# Sheet2.net
KiCad netlist of a schematic drawn in Altium Designer
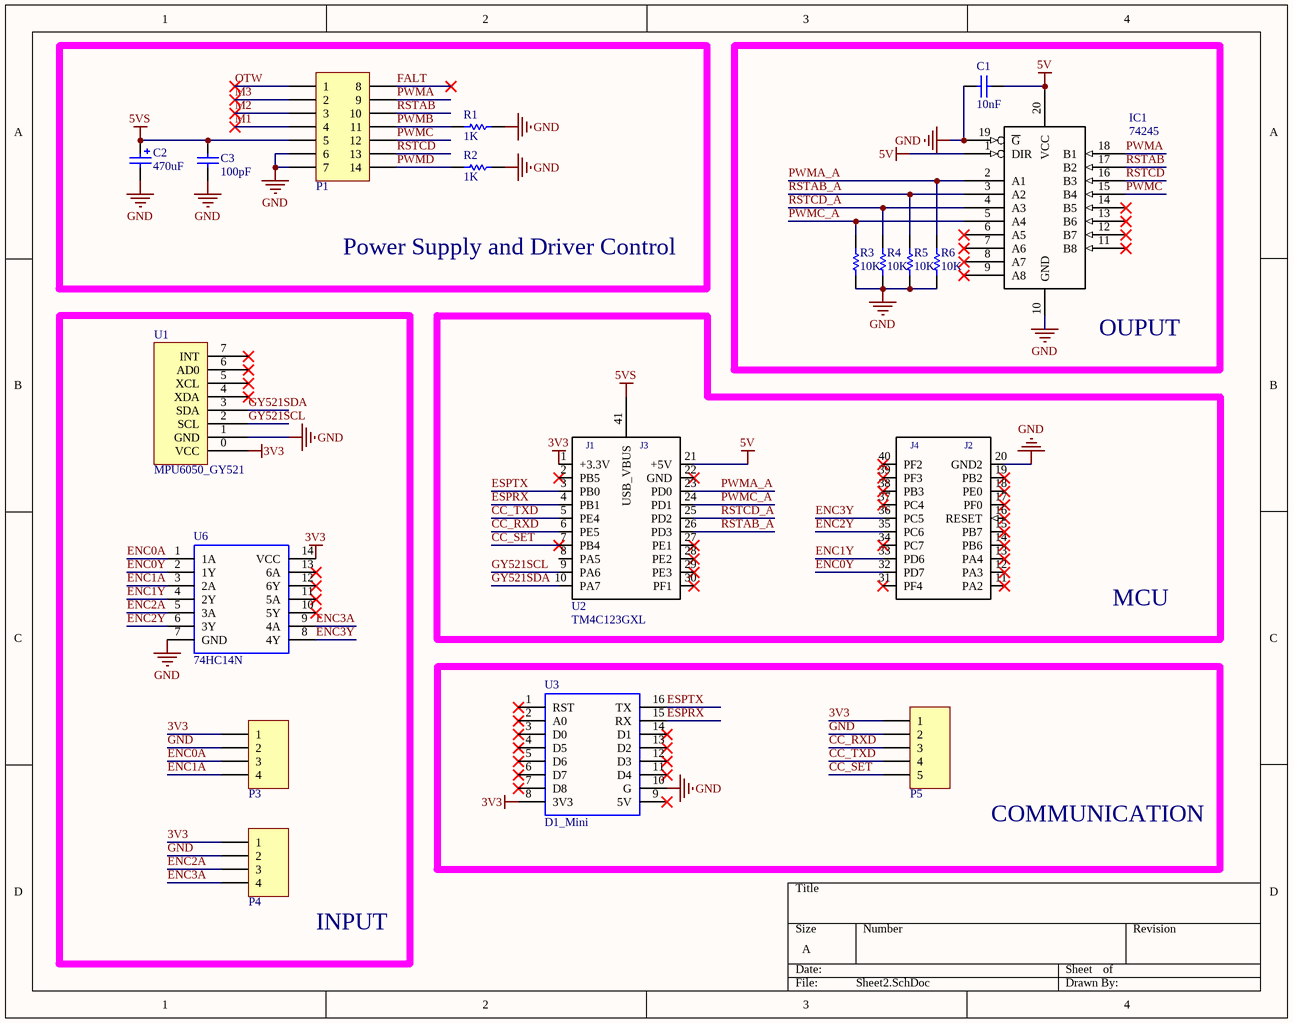
[diagram p0: Sheet2.SchDoc]

(export (version "E")
  (design (tool "Eeschema 10.0.6"))
  (components
    (comp (ref "C1")
      (value "10nF")
      (footprint "CAP-SM-0805")
      (description "Capacitor")
      (fields (field (name "Comment") "Cap Non-Pol SMD"))
      (libsource (lib "PIF_Library") (part "Cap Non-Pol SMD"))
    )
    (comp (ref "C2")
      (value "470uF")
      (footprint "CP1/2")
      (description "Polarized Capacitor (Radial)")
      (fields (field (name "Comment") "Cap Pol"))
      (libsource (lib "PIF_Library") (part "Cap Pol"))
    )
    (comp (ref "C3")
      (value "100pF")
      (footprint "CAP-SM-0805")
      (description "Capacitor")
      (fields (field (name "Comment") "Cap Non-Pol SMD"))
      (libsource (lib "PIF_Library") (part "Cap Non-Pol SMD"))
    )
    (comp (ref "IC1")
      (value "74245")
      (footprint "DIP20")
      (description "Octal bus tranceiver; 3-state")
      (fields (field (name "COPYRIGHT BY") "VanDungEvn@gmail.com"))
      (libsource (lib "My Library") (part "74245_1"))
    )
    (comp (ref "P1")
      (value "Header 7X2")
      (footprint "JP7X2")
      (description "Header, 7-Pin, Dual row")
      (fields (field (name "PUBLISHER") "Altium Limited"))
      (libsource (lib "PIF_Library") (part "Header 7X2"))
    )
    (comp (ref "P3")
      (value "Header 4H")
      (footprint "JP4H")
      (description "Header, 4-Pin, Right Angle")
      (fields (field (name "PUBLISHER") "Altium Limited"))
      (libsource (lib "PIF_Library") (part "Header 4H"))
    )
    (comp (ref "P4")
      (value "Header 4H")
      (footprint "JP4H")
      (description "Header, 4-Pin, Right Angle")
      (fields (field (name "PUBLISHER") "Altium Limited"))
      (libsource (lib "PIF_Library") (part "Header 4H"))
    )
    (comp (ref "P5")
      (value "Header 5")
      (footprint "JP5")
      (description "Header, 5-Pin")
      (fields (field (name "PUBLISHER") "Altium Limited"))
      (libsource (lib "PIF_Library") (part "Header 5"))
    )
    (comp (ref "R1")
      (value "1K")
      (footprint "RES 1/2W")
      (description "Resistor")
      (fields (field (name "Comment") "RESISTOR"))
      (libsource (lib "PIF_Library") (part "RESISTOR"))
    )
    (comp (ref "R2")
      (value "1K")
      (footprint "RES 1/2W")
      (description "Resistor")
      (fields (field (name "Comment") "RESISTOR"))
      (libsource (lib "PIF_Library") (part "RESISTOR"))
    )
    (comp (ref "R3")
      (value "10K")
      (footprint "RES 1/2W")
      (description "Resistor")
      (fields (field (name "Comment") "RESISTOR"))
      (libsource (lib "PIF_Library") (part "RESISTOR"))
    )
    (comp (ref "R4")
      (value "10K")
      (footprint "RES 1/2W")
      (description "Resistor")
      (fields (field (name "Comment") "RESISTOR"))
      (libsource (lib "PIF_Library") (part "RESISTOR"))
    )
    (comp (ref "R5")
      (value "10K")
      (footprint "RES 1/2W")
      (description "Resistor")
      (fields (field (name "Comment") "RESISTOR"))
      (libsource (lib "PIF_Library") (part "RESISTOR"))
    )
    (comp (ref "R6")
      (value "10K")
      (footprint "RES 1/2W")
      (description "Resistor")
      (fields (field (name "Comment") "RESISTOR"))
      (libsource (lib "PIF_Library") (part "RESISTOR"))
    )
    (comp (ref "U1")
      (value "MPU6050_GY521")
      (footprint "MPU6050_GY521")
      (libsource (lib "AltiumLib") (part "MPU6050_GY521"))
    )
    (comp (ref "U2")
      (value "TM4C123GXL")
      (footprint "EK-TM4C123GXL")
      (libsource (lib "AltiumLib") (part "EK-TM4C123GXL"))
    )
    (comp (ref "U3") (value "D1_Mini") (footprint "D1_Mini") (libsource (lib "AltiumLib") (part "D1_Mini")))
    (comp (ref "U6") (value "74HC14N") (footprint "74HC14N") (libsource (lib "AltiumLib") (part "74HC14N")))
  )
  (nets
    (net (code "1") (name "/CC_RXD") (class "Default")
      (node (ref "P5") (pin "3") (pinfunction "3_3") (pintype "passive"))
      (node (ref "U2") (pin "6") (pinfunction "PE5_6") (pintype "bidirectional"))
    )
    (net (code "2") (name "/CC_SET") (class "Default")
      (node (ref "P5") (pin "5") (pinfunction "5_5") (pintype "passive"))
      (node (ref "U2") (pin "7") (pinfunction "PB4_7") (pintype "bidirectional"))
    )
    (net (code "3") (name "/CC_TXD") (class "Default")
      (node (ref "P5") (pin "4") (pinfunction "4_4") (pintype "passive"))
      (node (ref "U2") (pin "5") (pinfunction "PE4_5") (pintype "bidirectional"))
    )
    (net (code "4") (name "/ENC0A") (class "Default")
      (node (ref "P3") (pin "3") (pinfunction "3_3") (pintype "passive"))
      (node (ref "U6") (pin "1") (pinfunction "1A_1") (pintype "passive"))
    )
    (net (code "5") (name "/ENC0Y") (class "Default")
      (node (ref "U2") (pin "32") (pinfunction "PD7_32") (pintype "bidirectional"))
      (node (ref "U6") (pin "2") (pinfunction "1Y_2") (pintype "passive"))
    )
    (net (code "6") (name "/ENC1A") (class "Default")
      (node (ref "P3") (pin "4") (pinfunction "4_4") (pintype "passive"))
      (node (ref "U6") (pin "3") (pinfunction "2A_3") (pintype "passive"))
    )
    (net (code "7") (name "/ENC1Y") (class "Default")
      (node (ref "U2") (pin "33") (pinfunction "PD6_33") (pintype "bidirectional"))
      (node (ref "U6") (pin "4") (pinfunction "2Y_4") (pintype "passive"))
    )
    (net (code "8") (name "/ENC2A") (class "Default")
      (node (ref "P4") (pin "3") (pinfunction "3_3") (pintype "passive"))
      (node (ref "U6") (pin "5") (pinfunction "3A_5") (pintype "passive"))
    )
    (net (code "9") (name "/ENC2Y") (class "Default")
      (node (ref "U2") (pin "35") (pinfunction "PC6_35") (pintype "bidirectional"))
      (node (ref "U6") (pin "6") (pinfunction "3Y_6") (pintype "passive"))
    )
    (net (code "10") (name "/ENC3A") (class "Default")
      (node (ref "P4") (pin "4") (pinfunction "4_4") (pintype "passive"))
      (node (ref "U6") (pin "9") (pinfunction "4A_9") (pintype "passive"))
    )
    (net (code "11") (name "/ENC3Y") (class "Default")
      (node (ref "U2") (pin "36") (pinfunction "PC5_36") (pintype "bidirectional"))
      (node (ref "U6") (pin "8") (pinfunction "4Y_8") (pintype "passive"))
    )
    (net (code "12") (name "/ESPRX") (class "Default")
      (node (ref "U2") (pin "4") (pinfunction "PB1_4") (pintype "bidirectional"))
      (node (ref "U3") (pin "15") (pinfunction "RX_15") (pintype "passive"))
    )
    (net (code "13") (name "/ESPTX") (class "Default")
      (node (ref "U2") (pin "3") (pinfunction "PB0_3") (pintype "bidirectional"))
      (node (ref "U3") (pin "16") (pinfunction "TX_16") (pintype "passive"))
    )
    (net (code "14") (name "/FALT") (class "Default")
      (node (ref "P1") (pin "8") (pinfunction "8_8") (pintype "passive+no_connect"))
    )
    (net (code "15") (name "/GY521SCL") (class "Default")
      (node (ref "U1") (pin "2") (pinfunction "SCL_2") (pintype "passive"))
      (node (ref "U2") (pin "9") (pinfunction "PA6_9") (pintype "bidirectional"))
    )
    (net (code "16") (name "/GY521SDA") (class "Default")
      (node (ref "U1") (pin "3") (pinfunction "SDA_3") (pintype "passive"))
      (node (ref "U2") (pin "10") (pinfunction "PA7_10") (pintype "bidirectional"))
    )
    (net (code "17") (name "/M1") (class "Default")
      (node (ref "P1") (pin "4") (pinfunction "4_4") (pintype "passive+no_connect"))
    )
    (net (code "18") (name "/M2") (class "Default")
      (node (ref "P1") (pin "3") (pinfunction "3_3") (pintype "passive+no_connect"))
    )
    (net (code "19") (name "/M3") (class "Default")
      (node (ref "P1") (pin "2") (pinfunction "2_2") (pintype "passive+no_connect"))
    )
    (net (code "20") (name "/OTW") (class "Default")
      (node (ref "P1") (pin "1") (pinfunction "1_1") (pintype "passive+no_connect"))
    )
    (net (code "21") (name "/PWMA") (class "Default")
      (node (ref "IC1") (pin "18") (pinfunction "B1_18") (pintype "input"))
      (node (ref "P1") (pin "9") (pinfunction "9_9") (pintype "passive"))
    )
    (net (code "22") (name "/PWMA_A") (class "Default")
      (node (ref "IC1") (pin "2") (pinfunction "A1_2") (pintype "tri_state"))
      (node (ref "R6") (pin "2") (pinfunction "2_2") (pintype "passive"))
      (node (ref "U2") (pin "23") (pinfunction "PD0_23") (pintype "bidirectional"))
    )
    (net (code "23") (name "/PWMB") (class "Default")
      (node (ref "P1") (pin "11") (pinfunction "11_11") (pintype "passive"))
      (node (ref "R1") (pin "1") (pinfunction "1_1") (pintype "passive"))
    )
    (net (code "24") (name "/PWMC") (class "Default")
      (node (ref "IC1") (pin "15") (pinfunction "B4_15") (pintype "input"))
      (node (ref "P1") (pin "12") (pinfunction "12_12") (pintype "passive"))
    )
    (net (code "25") (name "/PWMC_A") (class "Default")
      (node (ref "IC1") (pin "5") (pinfunction "A4_5") (pintype "tri_state"))
      (node (ref "R3") (pin "2") (pinfunction "2_2") (pintype "passive"))
      (node (ref "U2") (pin "24") (pinfunction "PD1_24") (pintype "bidirectional"))
    )
    (net (code "26") (name "/PWMD") (class "Default")
      (node (ref "P1") (pin "14") (pinfunction "14_14") (pintype "passive"))
      (node (ref "R2") (pin "1") (pinfunction "1_1") (pintype "passive"))
    )
    (net (code "27") (name "/RSTAB") (class "Default")
      (node (ref "IC1") (pin "17") (pinfunction "B2_17") (pintype "input"))
      (node (ref "P1") (pin "10") (pinfunction "10_10") (pintype "passive"))
    )
    (net (code "28") (name "/RSTAB_A") (class "Default")
      (node (ref "IC1") (pin "3") (pinfunction "A2_3") (pintype "tri_state"))
      (node (ref "R5") (pin "2") (pinfunction "2_2") (pintype "passive"))
      (node (ref "U2") (pin "26") (pinfunction "PD3_26") (pintype "bidirectional"))
    )
    (net (code "29") (name "/RSTCD") (class "Default")
      (node (ref "IC1") (pin "16") (pinfunction "B3_16") (pintype "input"))
      (node (ref "P1") (pin "13") (pinfunction "13_13") (pintype "passive"))
    )
    (net (code "30") (name "/RSTCD_A") (class "Default")
      (node (ref "IC1") (pin "4") (pinfunction "A3_4") (pintype "tri_state"))
      (node (ref "R4") (pin "2") (pinfunction "2_2") (pintype "passive"))
      (node (ref "U2") (pin "25") (pinfunction "PD2_25") (pintype "bidirectional"))
    )
    (net (code "31") (name "3V3") (class "Default")
      (node (ref "P3") (pin "1") (pinfunction "1_1") (pintype "passive"))
      (node (ref "P4") (pin "1") (pinfunction "1_1") (pintype "passive"))
      (node (ref "P5") (pin "1") (pinfunction "1_1") (pintype "passive"))
      (node (ref "U1") (pin "0") (pinfunction "VCC_0") (pintype "power_in"))
      (node (ref "U2") (pin "1") (pinfunction "+3.3V_1") (pintype "power_in"))
      (node (ref "U3") (pin "8") (pinfunction "3V3_8") (pintype "passive"))
      (node (ref "U6") (pin "14") (pinfunction "VCC_14") (pintype "passive"))
    )
    (net (code "32") (name "5V") (class "Default")
      (node (ref "C1") (pin "2") (pinfunction "2_2") (pintype "passive"))
      (node (ref "IC1") (pin "1") (pinfunction "DIR_1") (pintype "input"))
      (node (ref "IC1") (pin "20") (pinfunction "VCC_20") (pintype "power_in"))
      (node (ref "U2") (pin "21") (pinfunction "+5V_21") (pintype "power_in"))
    )
    (net (code "33") (name "5VS") (class "Default")
      (node (ref "C2") (pin "1") (pinfunction "1_1") (pintype "passive"))
      (node (ref "C3") (pin "2") (pinfunction "2_2") (pintype "passive"))
      (node (ref "P1") (pin "5") (pinfunction "5_5") (pintype "passive"))
      (node (ref "U2") (pin "41") (pinfunction "USB_VBUS_41") (pintype "passive"))
    )
    (net (code "34") (name "GND") (class "Default")
      (node (ref "C1") (pin "1") (pinfunction "1_1") (pintype "passive"))
      (node (ref "C2") (pin "2") (pinfunction "2_2") (pintype "passive"))
      (node (ref "C3") (pin "1") (pinfunction "1_1") (pintype "passive"))
      (node (ref "IC1") (pin "10") (pinfunction "GND_10") (pintype "power_in"))
      (node (ref "IC1") (pin "19") (pinfunction "~{G}_19") (pintype "input"))
      (node (ref "P1") (pin "6") (pinfunction "6_6") (pintype "passive"))
      (node (ref "P1") (pin "7") (pinfunction "7_7") (pintype "passive"))
      (node (ref "P3") (pin "2") (pinfunction "2_2") (pintype "passive"))
      (node (ref "P4") (pin "2") (pinfunction "2_2") (pintype "passive"))
      (node (ref "P5") (pin "2") (pinfunction "2_2") (pintype "passive"))
      (node (ref "R1") (pin "2") (pinfunction "2_2") (pintype "passive"))
      (node (ref "R2") (pin "2") (pinfunction "2_2") (pintype "passive"))
      (node (ref "R3") (pin "1") (pinfunction "1_1") (pintype "passive"))
      (node (ref "R4") (pin "1") (pinfunction "1_1") (pintype "passive"))
      (node (ref "R5") (pin "1") (pinfunction "1_1") (pintype "passive"))
      (node (ref "R6") (pin "1") (pinfunction "1_1") (pintype "passive"))
      (node (ref "U1") (pin "1") (pinfunction "GND_1") (pintype "power_in"))
      (node (ref "U2") (pin "20") (pinfunction "GND2_20") (pintype "power_in"))
      (node (ref "U3") (pin "10") (pinfunction "G_10") (pintype "passive"))
      (node (ref "U6") (pin "7") (pinfunction "GND_7") (pintype "passive"))
    )
    (net (code "35") (name "unconnected-(IC1-A5-Pad6)") (class "Default")
      (node (ref "IC1") (pin "6") (pinfunction "A5_6") (pintype "tri_state+no_connect"))
    )
    (net (code "36") (name "unconnected-(IC1-A6-Pad7)") (class "Default")
      (node (ref "IC1") (pin "7") (pinfunction "A6_7") (pintype "tri_state+no_connect"))
    )
    (net (code "37") (name "unconnected-(IC1-A7-Pad8)") (class "Default")
      (node (ref "IC1") (pin "8") (pinfunction "A7_8") (pintype "tri_state+no_connect"))
    )
    (net (code "38") (name "unconnected-(IC1-A8-Pad9)") (class "Default")
      (node (ref "IC1") (pin "9") (pinfunction "A8_9") (pintype "tri_state+no_connect"))
    )
    (net (code "39") (name "unconnected-(IC1-B5-Pad14)") (class "Default")
      (node (ref "IC1") (pin "14") (pinfunction "B5_14") (pintype "input+no_connect"))
    )
    (net (code "40") (name "unconnected-(IC1-B6-Pad13)") (class "Default")
      (node (ref "IC1") (pin "13") (pinfunction "B6_13") (pintype "input+no_connect"))
    )
    (net (code "41") (name "unconnected-(IC1-B7-Pad12)") (class "Default")
      (node (ref "IC1") (pin "12") (pinfunction "B7_12") (pintype "input+no_connect"))
    )
    (net (code "42") (name "unconnected-(IC1-B8-Pad11)") (class "Default")
      (node (ref "IC1") (pin "11") (pinfunction "B8_11") (pintype "input+no_connect"))
    )
    (net (code "43") (name "unconnected-(U1-AD0-Pad6)") (class "Default")
      (node (ref "U1") (pin "6") (pinfunction "AD0_6") (pintype "passive+no_connect"))
    )
    (net (code "44") (name "unconnected-(U1-INT-Pad7)") (class "Default")
      (node (ref "U1") (pin "7") (pinfunction "INT_7") (pintype "passive+no_connect"))
    )
    (net (code "45") (name "unconnected-(U1-XCL-Pad5)") (class "Default")
      (node (ref "U1") (pin "5") (pinfunction "XCL_5") (pintype "passive+no_connect"))
    )
    (net (code "46") (name "unconnected-(U1-XDA-Pad4)") (class "Default")
      (node (ref "U1") (pin "4") (pinfunction "XDA_4") (pintype "passive+no_connect"))
    )
    (net (code "47") (name "unconnected-(U2-GND-Pad22)") (class "Default")
      (node (ref "U2") (pin "22") (pinfunction "GND_22") (pintype "power_in+no_connect"))
    )
    (net (code "48") (name "unconnected-(U2-PA2-Pad11)") (class "Default")
      (node (ref "U2") (pin "11") (pinfunction "PA2_11") (pintype "bidirectional+no_connect"))
    )
    (net (code "49") (name "unconnected-(U2-PA3-Pad12)") (class "Default")
      (node (ref "U2") (pin "12") (pinfunction "PA3_12") (pintype "bidirectional+no_connect"))
    )
    (net (code "50") (name "unconnected-(U2-PA4-Pad13)") (class "Default")
      (node (ref "U2") (pin "13") (pinfunction "PA4_13") (pintype "bidirectional+no_connect"))
    )
    (net (code "51") (name "unconnected-(U2-PA5-Pad8)") (class "Default")
      (node (ref "U2") (pin "8") (pinfunction "PA5_8") (pintype "bidirectional"))
    )
    (net (code "52") (name "unconnected-(U2-PB2-Pad19)") (class "Default")
      (node (ref "U2") (pin "19") (pinfunction "PB2_19") (pintype "bidirectional+no_connect"))
    )
    (net (code "53") (name "unconnected-(U2-PB3-Pad38)") (class "Default")
      (node (ref "U2") (pin "38") (pinfunction "PB3_38") (pintype "bidirectional+no_connect"))
    )
    (net (code "54") (name "unconnected-(U2-PB5-Pad2)") (class "Default")
      (node (ref "U2") (pin "2") (pinfunction "PB5_2") (pintype "bidirectional+no_connect"))
    )
    (net (code "55") (name "unconnected-(U2-PB6-Pad14)") (class "Default")
      (node (ref "U2") (pin "14") (pinfunction "PB6_14") (pintype "bidirectional+no_connect"))
    )
    (net (code "56") (name "unconnected-(U2-PB7-Pad15)") (class "Default")
      (node (ref "U2") (pin "15") (pinfunction "PB7_15") (pintype "bidirectional+no_connect"))
    )
    (net (code "57") (name "unconnected-(U2-PC4-Pad37)") (class "Default")
      (node (ref "U2") (pin "37") (pinfunction "PC4_37") (pintype "bidirectional+no_connect"))
    )
    (net (code "58") (name "unconnected-(U2-PC7-Pad34)") (class "Default")
      (node (ref "U2") (pin "34") (pinfunction "PC7_34") (pintype "bidirectional+no_connect"))
    )
    (net (code "59") (name "unconnected-(U2-PE0-Pad18)") (class "Default")
      (node (ref "U2") (pin "18") (pinfunction "PE0_18") (pintype "bidirectional+no_connect"))
    )
    (net (code "60") (name "unconnected-(U2-PE1-Pad27)") (class "Default")
      (node (ref "U2") (pin "27") (pinfunction "PE1_27") (pintype "bidirectional+no_connect"))
    )
    (net (code "61") (name "unconnected-(U2-PE2-Pad28)") (class "Default")
      (node (ref "U2") (pin "28") (pinfunction "PE2_28") (pintype "bidirectional+no_connect"))
    )
    (net (code "62") (name "unconnected-(U2-PE3-Pad29)") (class "Default")
      (node (ref "U2") (pin "29") (pinfunction "PE3_29") (pintype "bidirectional+no_connect"))
    )
    (net (code "63") (name "unconnected-(U2-PF0-Pad17)") (class "Default")
      (node (ref "U2") (pin "17") (pinfunction "PF0_17") (pintype "bidirectional+no_connect"))
    )
    (net (code "64") (name "unconnected-(U2-PF1-Pad30)") (class "Default")
      (node (ref "U2") (pin "30") (pinfunction "PF1_30") (pintype "bidirectional+no_connect"))
    )
    (net (code "65") (name "unconnected-(U2-PF2-Pad40)") (class "Default")
      (node (ref "U2") (pin "40") (pinfunction "PF2_40") (pintype "bidirectional+no_connect"))
    )
    (net (code "66") (name "unconnected-(U2-PF3-Pad39)") (class "Default")
      (node (ref "U2") (pin "39") (pinfunction "PF3_39") (pintype "bidirectional+no_connect"))
    )
    (net (code "67") (name "unconnected-(U2-PF4-Pad31)") (class "Default")
      (node (ref "U2") (pin "31") (pinfunction "PF4_31") (pintype "bidirectional+no_connect"))
    )
    (net (code "68") (name "unconnected-(U2-RESET-Pad16)") (class "Default")
      (node (ref "U2") (pin "16") (pinfunction "RESET_16") (pintype "input+no_connect"))
    )
    (net (code "69") (name "unconnected-(U3-5V-Pad9)") (class "Default")
      (node (ref "U3") (pin "9") (pinfunction "5V_9") (pintype "passive+no_connect"))
    )
    (net (code "70") (name "unconnected-(U3-A0-Pad2)") (class "Default")
      (node (ref "U3") (pin "2") (pinfunction "A0_2") (pintype "passive+no_connect"))
    )
    (net (code "71") (name "unconnected-(U3-D0-Pad3)") (class "Default")
      (node (ref "U3") (pin "3") (pinfunction "D0_3") (pintype "passive+no_connect"))
    )
    (net (code "72") (name "unconnected-(U3-D1-Pad14)") (class "Default")
      (node (ref "U3") (pin "14") (pinfunction "D1_14") (pintype "passive+no_connect"))
    )
    (net (code "73") (name "unconnected-(U3-D2-Pad13)") (class "Default")
      (node (ref "U3") (pin "13") (pinfunction "D2_13") (pintype "passive+no_connect"))
    )
    (net (code "74") (name "unconnected-(U3-D3-Pad12)") (class "Default")
      (node (ref "U3") (pin "12") (pinfunction "D3_12") (pintype "passive+no_connect"))
    )
    (net (code "75") (name "unconnected-(U3-D4-Pad11)") (class "Default")
      (node (ref "U3") (pin "11") (pinfunction "D4_11") (pintype "passive+no_connect"))
    )
    (net (code "76") (name "unconnected-(U3-D5-Pad4)") (class "Default")
      (node (ref "U3") (pin "4") (pinfunction "D5_4") (pintype "passive+no_connect"))
    )
    (net (code "77") (name "unconnected-(U3-D6-Pad5)") (class "Default")
      (node (ref "U3") (pin "5") (pinfunction "D6_5") (pintype "passive+no_connect"))
    )
    (net (code "78") (name "unconnected-(U3-D7-Pad6)") (class "Default")
      (node (ref "U3") (pin "6") (pinfunction "D7_6") (pintype "passive+no_connect"))
    )
    (net (code "79") (name "unconnected-(U3-D8-Pad7)") (class "Default")
      (node (ref "U3") (pin "7") (pinfunction "D8_7") (pintype "passive+no_connect"))
    )
    (net (code "80") (name "unconnected-(U3-RST-Pad1)") (class "Default")
      (node (ref "U3") (pin "1") (pinfunction "RST_1") (pintype "passive+no_connect"))
    )
    (net (code "81") (name "unconnected-(U6-5A-Pad11)") (class "Default")
      (node (ref "U6") (pin "11") (pinfunction "5A_11") (pintype "passive+no_connect"))
    )
    (net (code "82") (name "unconnected-(U6-5Y-Pad10)") (class "Default")
      (node (ref "U6") (pin "10") (pinfunction "5Y_10") (pintype "passive+no_connect"))
    )
    (net (code "83") (name "unconnected-(U6-6A-Pad13)") (class "Default")
      (node (ref "U6") (pin "13") (pinfunction "6A_13") (pintype "passive+no_connect"))
    )
    (net (code "84") (name "unconnected-(U6-6Y-Pad12)") (class "Default")
      (node (ref "U6") (pin "12") (pinfunction "6Y_12") (pintype "passive+no_connect"))
    )
  )
)
